# PRIMERPROYECTO.net
KiCad netlist of a schematic drawn in Altium Designer
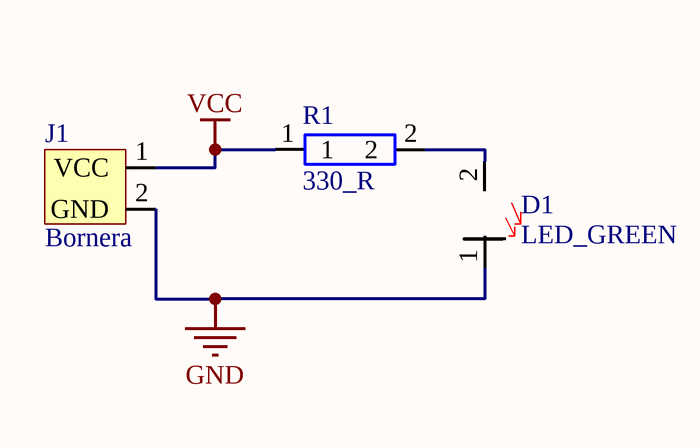
[diagram p0: PRIMERPROYECTO.SchDoc]

(export (version "E")
  (design (tool "Eeschema 10.0.6"))
  (components
    (comp (ref "D1")
      (value "LED_GREEN")
      (footprint "LED_GREEN")
      (libsource (lib "PRIMERPROYECTO") (part "LED_GREEN"))
    )
    (comp (ref "J1")
      (value "Bornera")
      (footprint "Bornera_azul_2pines")
      (libsource (lib "PRIMERPROYECTO") (part "Bornera_azul_2pines"))
    )
    (comp (ref "R1")
      (value "330_R")
      (footprint "330R_0.25W")
      (libsource (lib "PRIMERPROYECTO") (part "330R_0.25W"))
    )
  )
  (nets
    (net (code "1") (name "GND") (class "Default")
      (node (ref "D1") (pin "1") (pinfunction "C_1") (pintype "passive"))
      (node (ref "J1") (pin "2") (pinfunction "GND_2") (pintype "passive"))
    )
    (net (code "2") (name "Net-(D1-A)") (class "Default")
      (node (ref "D1") (pin "2") (pinfunction "A_2") (pintype "passive"))
      (node (ref "R1") (pin "2") (pinfunction "2_2") (pintype "passive"))
    )
    (net (code "3") (name "VCC") (class "Default")
      (node (ref "J1") (pin "1") (pinfunction "VCC_1") (pintype "passive"))
      (node (ref "R1") (pin "1") (pinfunction "1_1") (pintype "passive"))
    )
  )
)
